# LIC_rack_BM4.net
KiCad netlist of a schematic drawn in EAGLE
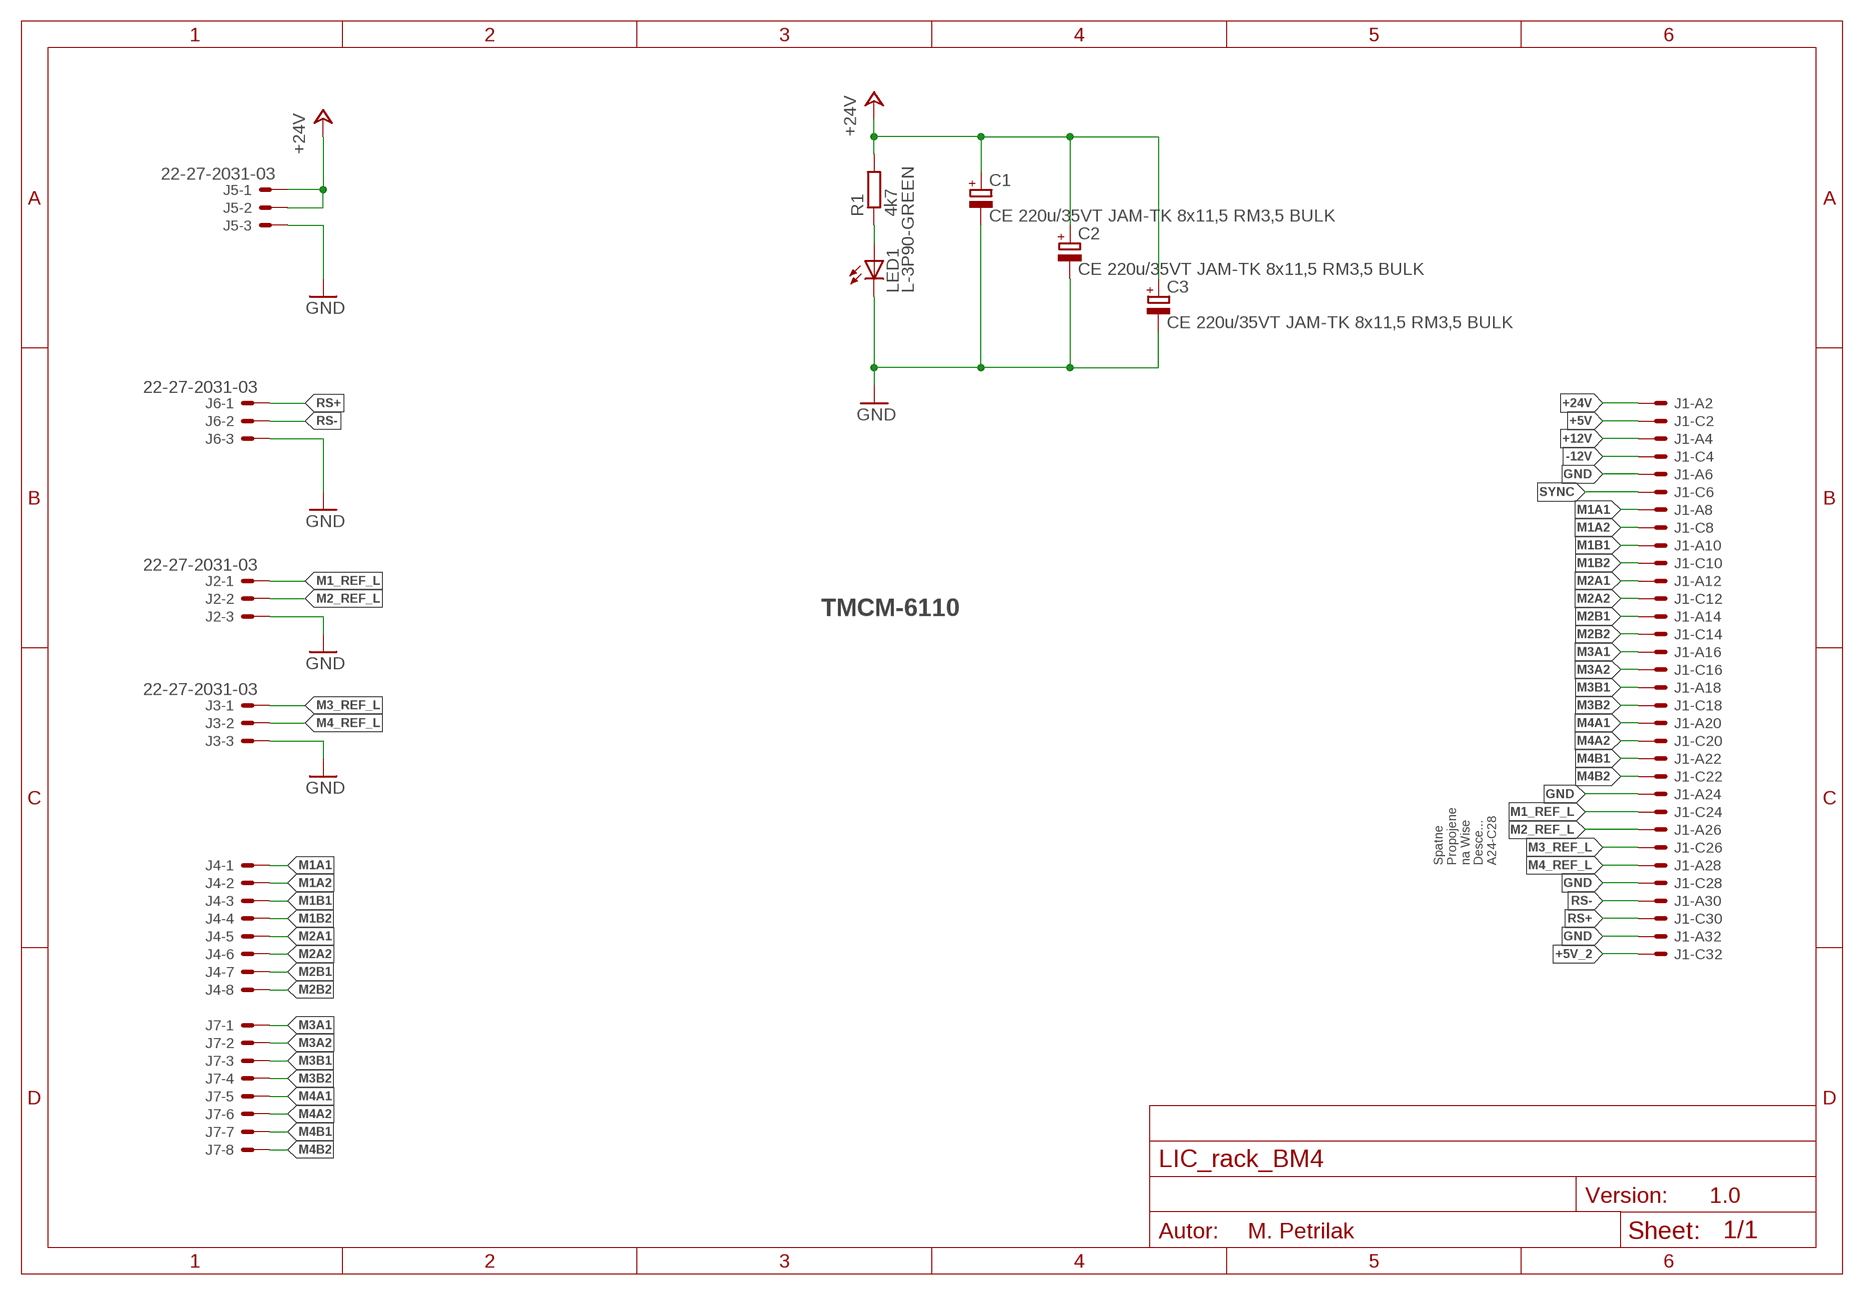
[diagram p0: schematic, sheet 1]

(export (version "E")
  (design (tool "Eeschema 10.0.6"))
  (components
    (comp (ref "C1")
      (value "CE 220u/35VT JAM-TK 8x11,5 RM3,5 BULK")
      (footprint "eagle-import:E3,5-8L")
      (libsource (lib "eagle-import") (part "CPOL-EUE3.5-8L"))
    )
    (comp (ref "C2")
      (value "CE 220u/35VT JAM-TK 8x11,5 RM3,5 BULK")
      (footprint "eagle-import:E3,5-8L")
      (libsource (lib "eagle-import") (part "CPOL-EUE3.5-8L"))
    )
    (comp (ref "C3")
      (value "CE 220u/35VT JAM-TK 8x11,5 RM3,5 BULK")
      (footprint "eagle-import:E3,5-8L")
      (libsource (lib "eagle-import") (part "CPOL-EUE3.5-8L"))
    )
    (comp (ref "J1")
      (value "VG32SP")
      (footprint "eagle-import:VG32P")
      (libsource (lib "eagle-import") (part "VG32SP"))
    )
    (comp (ref "J2")
      (value "22-27-2031-03")
      (footprint "eagle-import:6410-03")
      (libsource (lib "eagle-import") (part "22-?-0327-2031"))
    )
    (comp (ref "J3")
      (value "22-27-2031-03")
      (footprint "eagle-import:6410-03")
      (libsource (lib "eagle-import") (part "22-?-0327-2031"))
    )
    (comp (ref "J4")
      (value "22-27-2081-08")
      (footprint "eagle-import:6410-08")
      (libsource (lib "eagle-import") (part "22-?-0827-2081"))
    )
    (comp (ref "J5")
      (value "22-27-2031-03")
      (footprint "eagle-import:6410-03")
      (libsource (lib "eagle-import") (part "22-?-0327-2031"))
    )
    (comp (ref "J6")
      (value "22-27-2031-03")
      (footprint "eagle-import:6410-03")
      (libsource (lib "eagle-import") (part "22-?-0327-2031"))
    )
    (comp (ref "J7")
      (value "22-27-2081-08")
      (footprint "eagle-import:6410-08")
      (libsource (lib "eagle-import") (part "22-?-0827-2081"))
    )
    (comp (ref "LED1")
      (value "L-3P90-GREEN")
      (footprint "eagle-import:L-3P90")
      (libsource (lib "eagle-import") (part "L-3P90-GREEN"))
    )
    (comp (ref "R1")
      (value "4k7")
      (footprint "eagle-import:R1206")
      (libsource (lib "eagle-import") (part "R-EU_R1206"))
    )
  )
  (nets
    (net (code "1") (name "+5V") (class "Default")
      (node (ref "J1") (pin "C2") (pinfunction "MS_C2") (pintype "passive"))
    )
    (net (code "2") (name "+5V_2") (class "Default")
      (node (ref "J1") (pin "C32") (pinfunction "MSV_C32") (pintype "passive"))
    )
    (net (code "3") (name "+12V") (class "Default")
      (node (ref "J1") (pin "A4") (pinfunction "MS_A4") (pintype "passive"))
    )
    (net (code "4") (name "+24V") (class "Default")
      (node (ref "C1") (pin "+") (pinfunction "+_+") (pintype "passive"))
      (node (ref "C2") (pin "+") (pinfunction "+_+") (pintype "passive"))
      (node (ref "C3") (pin "+") (pinfunction "+_+") (pintype "passive"))
      (node (ref "J1") (pin "A2") (pinfunction "MS_A2") (pintype "passive"))
      (node (ref "J5") (pin "1") (pinfunction "S_1") (pintype "passive"))
      (node (ref "J5") (pin "2") (pinfunction "S_2") (pintype "passive"))
      (node (ref "R1") (pin "2") (pinfunction "2_2") (pintype "passive"))
    )
    (net (code "5") (name "-12V") (class "Default")
      (node (ref "J1") (pin "C4") (pinfunction "MS_C4") (pintype "passive"))
    )
    (net (code "6") (name "GND") (class "Default")
      (node (ref "C1") (pin "-") (pinfunction "-_-") (pintype "passive"))
      (node (ref "C2") (pin "-") (pinfunction "-_-") (pintype "passive"))
      (node (ref "C3") (pin "-") (pinfunction "-_-") (pintype "passive"))
      (node (ref "J1") (pin "A24") (pinfunction "MS_A24") (pintype "passive"))
      (node (ref "J1") (pin "A32") (pinfunction "MS_A32") (pintype "passive"))
      (node (ref "J1") (pin "A6") (pinfunction "MS_A6") (pintype "passive"))
      (node (ref "J1") (pin "C28") (pinfunction "MS_C28") (pintype "passive"))
      (node (ref "J2") (pin "3") (pinfunction "S_3") (pintype "passive"))
      (node (ref "J3") (pin "3") (pinfunction "S_3") (pintype "passive"))
      (node (ref "J5") (pin "3") (pinfunction "S_3") (pintype "passive"))
      (node (ref "J6") (pin "3") (pinfunction "S_3") (pintype "passive"))
      (node (ref "LED1") (pin "K") (pinfunction "C_K") (pintype "passive"))
    )
    (net (code "7") (name "M1A1") (class "Default")
      (node (ref "J1") (pin "A8") (pinfunction "MS_A8") (pintype "passive"))
      (node (ref "J4") (pin "1") (pinfunction "S_1") (pintype "passive"))
    )
    (net (code "8") (name "M1A2") (class "Default")
      (node (ref "J1") (pin "C8") (pinfunction "MS_C8") (pintype "passive"))
      (node (ref "J4") (pin "2") (pinfunction "S_2") (pintype "passive"))
    )
    (net (code "9") (name "M1B1") (class "Default")
      (node (ref "J1") (pin "A10") (pinfunction "MS_A10") (pintype "passive"))
      (node (ref "J4") (pin "3") (pinfunction "S_3") (pintype "passive"))
    )
    (net (code "10") (name "M1B2") (class "Default")
      (node (ref "J1") (pin "C10") (pinfunction "MS_C10") (pintype "passive"))
      (node (ref "J4") (pin "4") (pinfunction "S_4") (pintype "passive"))
    )
    (net (code "11") (name "M1_REF_L") (class "Default")
      (node (ref "J1") (pin "C24") (pinfunction "MS_C24") (pintype "passive"))
      (node (ref "J2") (pin "1") (pinfunction "S_1") (pintype "passive"))
    )
    (net (code "12") (name "M2A1") (class "Default")
      (node (ref "J1") (pin "A12") (pinfunction "MS_A12") (pintype "passive"))
      (node (ref "J4") (pin "5") (pinfunction "S_5") (pintype "passive"))
    )
    (net (code "13") (name "M2A2") (class "Default")
      (node (ref "J1") (pin "C12") (pinfunction "MS_C12") (pintype "passive"))
      (node (ref "J4") (pin "6") (pinfunction "S_6") (pintype "passive"))
    )
    (net (code "14") (name "M2B1") (class "Default")
      (node (ref "J1") (pin "A14") (pinfunction "MS_A14") (pintype "passive"))
      (node (ref "J4") (pin "7") (pinfunction "S_7") (pintype "passive"))
    )
    (net (code "15") (name "M2B2") (class "Default")
      (node (ref "J1") (pin "C14") (pinfunction "MS_C14") (pintype "passive"))
      (node (ref "J4") (pin "8") (pinfunction "S_8") (pintype "passive"))
    )
    (net (code "16") (name "M2_REF_L") (class "Default")
      (node (ref "J1") (pin "A26") (pinfunction "MS_A26") (pintype "passive"))
      (node (ref "J2") (pin "2") (pinfunction "S_2") (pintype "passive"))
    )
    (net (code "17") (name "M3A1") (class "Default")
      (node (ref "J1") (pin "A16") (pinfunction "MS_A16") (pintype "passive"))
      (node (ref "J7") (pin "1") (pinfunction "S_1") (pintype "passive"))
    )
    (net (code "18") (name "M3A2") (class "Default")
      (node (ref "J1") (pin "C16") (pinfunction "MS_C16") (pintype "passive"))
      (node (ref "J7") (pin "2") (pinfunction "S_2") (pintype "passive"))
    )
    (net (code "19") (name "M3B1") (class "Default")
      (node (ref "J1") (pin "A18") (pinfunction "MS_A18") (pintype "passive"))
      (node (ref "J7") (pin "3") (pinfunction "S_3") (pintype "passive"))
    )
    (net (code "20") (name "M3B2") (class "Default")
      (node (ref "J1") (pin "C18") (pinfunction "MS_C18") (pintype "passive"))
      (node (ref "J7") (pin "4") (pinfunction "S_4") (pintype "passive"))
    )
    (net (code "21") (name "M3_REF_L") (class "Default")
      (node (ref "J1") (pin "C26") (pinfunction "MS_C26") (pintype "passive"))
      (node (ref "J3") (pin "1") (pinfunction "S_1") (pintype "passive"))
    )
    (net (code "22") (name "M4A1") (class "Default")
      (node (ref "J1") (pin "A20") (pinfunction "MS_A20") (pintype "passive"))
      (node (ref "J7") (pin "5") (pinfunction "S_5") (pintype "passive"))
    )
    (net (code "23") (name "M4A2") (class "Default")
      (node (ref "J1") (pin "C20") (pinfunction "MS_C20") (pintype "passive"))
      (node (ref "J7") (pin "6") (pinfunction "S_6") (pintype "passive"))
    )
    (net (code "24") (name "M4B1") (class "Default")
      (node (ref "J1") (pin "A22") (pinfunction "MS_A22") (pintype "passive"))
      (node (ref "J7") (pin "7") (pinfunction "S_7") (pintype "passive"))
    )
    (net (code "25") (name "M4B2") (class "Default")
      (node (ref "J1") (pin "C22") (pinfunction "MS_C22") (pintype "passive"))
      (node (ref "J7") (pin "8") (pinfunction "S_8") (pintype "passive"))
    )
    (net (code "26") (name "M4_REF_L") (class "Default")
      (node (ref "J1") (pin "A28") (pinfunction "MS_A28") (pintype "passive"))
      (node (ref "J3") (pin "2") (pinfunction "S_2") (pintype "passive"))
    )
    (net (code "27") (name "Net-(LED1-PadA)") (class "Default")
      (node (ref "LED1") (pin "A") (pinfunction "A_A") (pintype "passive"))
      (node (ref "R1") (pin "1") (pinfunction "1_1") (pintype "passive"))
    )
    (net (code "28") (name "RS+") (class "Default")
      (node (ref "J1") (pin "C30") (pinfunction "MS_C30") (pintype "passive"))
      (node (ref "J6") (pin "1") (pinfunction "S_1") (pintype "passive"))
    )
    (net (code "29") (name "RS-") (class "Default")
      (node (ref "J1") (pin "A30") (pinfunction "MS_A30") (pintype "passive"))
      (node (ref "J6") (pin "2") (pinfunction "S_2") (pintype "passive"))
    )
    (net (code "30") (name "SYNC") (class "Default")
      (node (ref "J1") (pin "C6") (pinfunction "MS_C6") (pintype "passive"))
    )
  )
)
